# Sheet1.net
KiCad netlist of a schematic drawn in Altium Designer
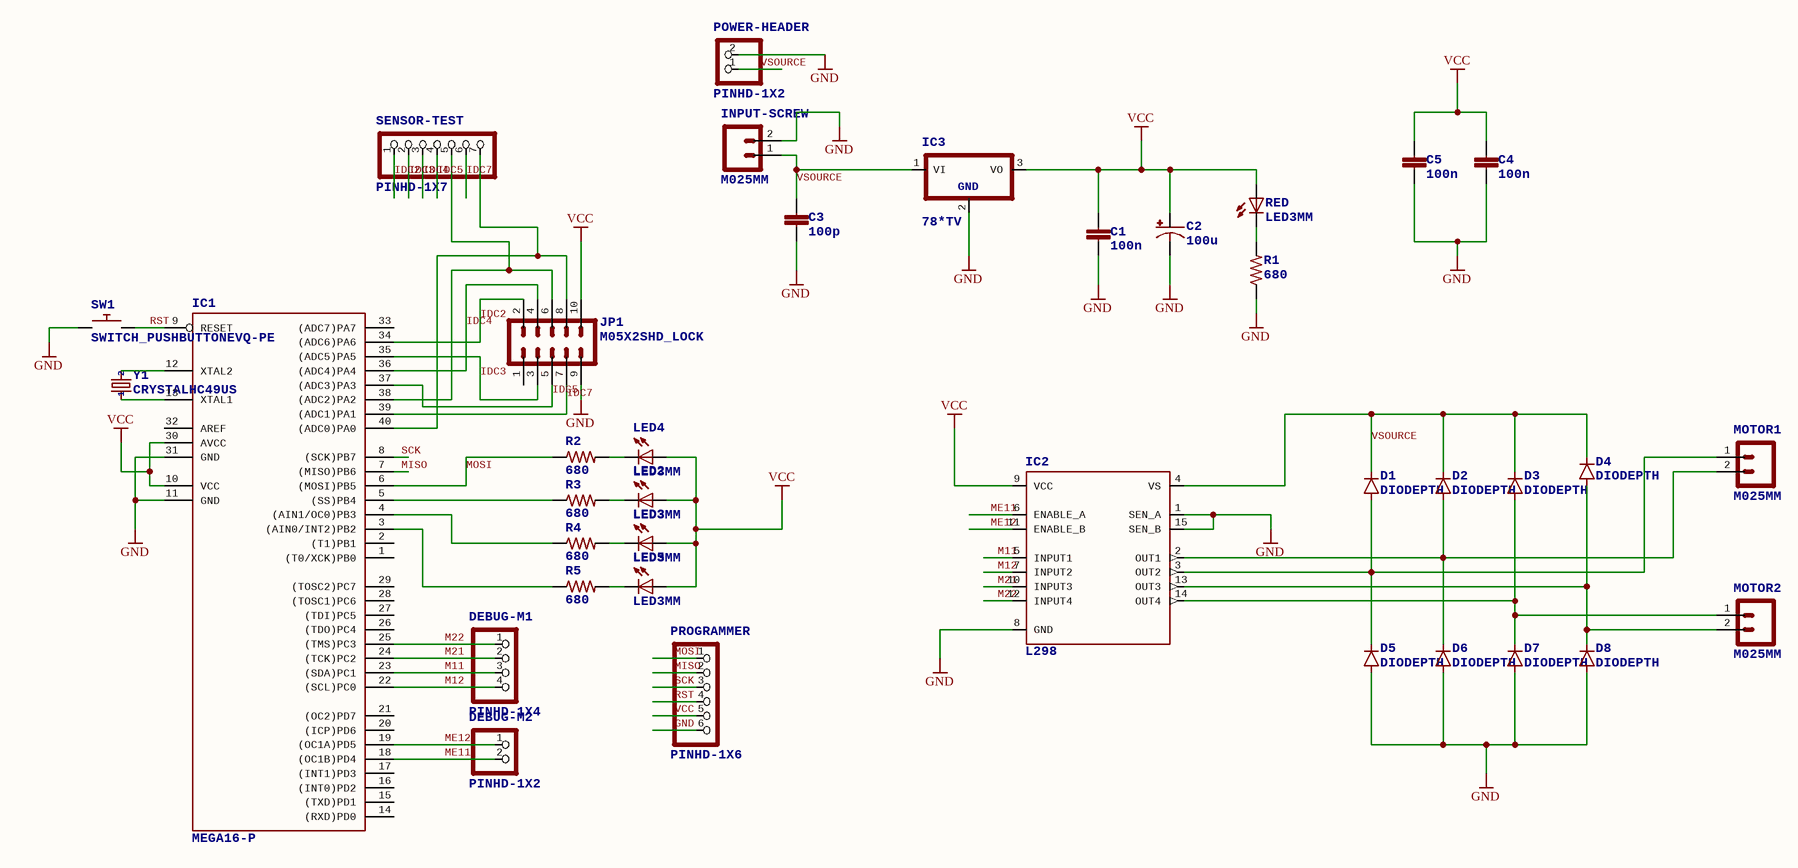
[diagram p0: Sheet1.SchDoc]

(export (version "E")
  (design (tool "Eeschema 10.0.6"))
  (components
    (comp (ref "C1")
      (value "100n")
      (footprint "CAP-PTH-SMALL")
      (description "CapacitorStandard 0603 ceramic capacitor, and 0.1\" leaded capacitor.")
      (libsource (lib "SparkFun-Passives") (part "CAPPTH"))
    )
    (comp (ref "C2")
      (value "100u")
      (footprint "CPOL-RADIAL-100UF-25V")
      (libsource (lib "SparkFun-Passives") (part "CAP_POLPTH1"))
    )
    (comp (ref "C3")
      (value "100p")
      (footprint "CAP-PTH-SMALL")
      (description "CapacitorStandard 0603 ceramic capacitor, and 0.1\" leaded capacitor.")
      (libsource (lib "") (part "CAPPTH_1"))
    )
    (comp (ref "C4")
      (value "100n")
      (footprint "CAP-PTH-SMALL")
      (description "CapacitorStandard 0603 ceramic capacitor, and 0.1\" leaded capacitor.")
      (libsource (lib "SparkFun-Capacitors") (part "CAPPTH"))
    )
    (comp (ref "C5")
      (value "100n")
      (footprint "CAP-PTH-SMALL")
      (description "CapacitorStandard 0603 ceramic capacitor, and 0.1\" leaded capacitor.")
      (libsource (lib "SparkFun-Capacitors") (part "CAPPTH"))
    )
    (comp (ref "D1")
      (value "DIODEPTH")
      (footprint "DIODE-1N4001")
      (libsource (lib "SparkFun-DiscreteSemi") (part "DIODEPTH"))
    )
    (comp (ref "D2")
      (value "DIODEPTH")
      (footprint "DIODE-1N4001")
      (libsource (lib "SparkFun-DiscreteSemi") (part "DIODEPTH"))
    )
    (comp (ref "D3")
      (value "DIODEPTH")
      (footprint "DIODE-1N4001")
      (libsource (lib "SparkFun-DiscreteSemi") (part "DIODEPTH"))
    )
    (comp (ref "D4")
      (value "DIODEPTH")
      (footprint "DIODE-1N4001")
      (libsource (lib "SparkFun-DiscreteSemi") (part "DIODEPTH"))
    )
    (comp (ref "D5")
      (value "DIODEPTH")
      (footprint "DIODE-1N4001")
      (libsource (lib "SparkFun-DiscreteSemi") (part "DIODEPTH"))
    )
    (comp (ref "D6")
      (value "DIODEPTH")
      (footprint "DIODE-1N4001")
      (libsource (lib "SparkFun-DiscreteSemi") (part "DIODEPTH"))
    )
    (comp (ref "D7")
      (value "DIODEPTH")
      (footprint "DIODE-1N4001")
      (libsource (lib "SparkFun-DiscreteSemi") (part "DIODEPTH"))
    )
    (comp (ref "D8")
      (value "DIODEPTH")
      (footprint "DIODE-1N4001")
      (libsource (lib "SparkFun-DiscreteSemi") (part "DIODEPTH"))
    )
    (comp (ref "DEBUG-M1")
      (value "PINHD-1X4")
      (footprint "1X04")
      (description "PIN HEADER")
      (libsource (lib "pinhead") (part "PINHD-1X4"))
    )
    (comp (ref "DEBUG-M2")
      (value "PINHD-1X2")
      (footprint "1X02")
      (description "PIN HEADER")
      (libsource (lib "pinhead") (part "PINHD-1X2"))
    )
    (comp (ref "IC1")
      (value "MEGA16-P")
      (footprint "DIL40")
      (fields (field (name "MPN") "ATMEGA16-16PU"))
      (libsource (lib "atmel") (part "MEGA16-P"))
    )
    (comp (ref "IC2")
      (value "L298")
      (footprint "MULTIWATT-15")
      (description "DUAL FULL-BRIDGE DRIVER")
      (fields (field (name "MPN") "L298N"))
      (libsource (lib "st-microelectronics") (part "L298"))
    )
    (comp (ref "IC3")
      (value "78*TV")
      (footprint "TO220V")
      (fields (field (name "GND") "GND"))
      (libsource (lib "linear") (part "78*TV"))
    )
    (comp (ref "INPUT-SCREW")
      (value "M025MM")
      (footprint "SCREWTERMINAL-5MM-2")
      (libsource (lib "SparkFun-Connectors") (part "M025MM"))
    )
    (comp (ref "JP1")
      (value "M05X2SHD_LOCK")
      (footprint "2X5-SHROUDED_LOCK")
      (libsource (lib "SparkFun-Connectors") (part "M05X2SHD_LOCK"))
    )
    (comp (ref "LED2") (value "LED3MM") (footprint "LED3MM") (libsource (lib "adafruit") (part "LED3MM")))
    (comp (ref "LED3") (value "LED3MM") (footprint "LED3MM") (libsource (lib "adafruit") (part "LED3MM")))
    (comp (ref "LED4") (value "LED3MM") (footprint "LED3MM") (libsource (lib "adafruit") (part "LED3MM")))
    (comp (ref "LED5") (value "LED3MM") (footprint "LED3MM") (libsource (lib "adafruit") (part "LED3MM")))
    (comp (ref "MOTOR1")
      (value "M025MM")
      (footprint "SCREWTERMINAL-5MM-2")
      (libsource (lib "SparkFun-Connectors") (part "M025MM"))
    )
    (comp (ref "MOTOR2")
      (value "M025MM")
      (footprint "SCREWTERMINAL-5MM-2")
      (libsource (lib "SparkFun-Connectors") (part "M025MM"))
    )
    (comp (ref "POWER-HEADER")
      (value "PINHD-1X2")
      (footprint "1X02")
      (description "PIN HEADER")
      (libsource (lib "pinhead") (part "PINHD-1X2"))
    )
    (comp (ref "PROGRAMMER")
      (value "PINHD-1X6")
      (footprint "1X06")
      (description "PIN HEADER")
      (libsource (lib "adafruit") (part "PINHD-1X6"))
    )
    (comp (ref "R1")
      (value "680")
      (footprint "AXIAL-0.3")
      (description "RES-12182")
      (libsource (lib "SparkFun-Resistors") (part "1KOHM-1/4W-1%(PTH)"))
    )
    (comp (ref "R2")
      (value "680")
      (footprint "AXIAL-0.3")
      (description "RES-12182")
      (libsource (lib "SparkFun-Resistors") (part "1KOHM-1/4W-1%(PTH)"))
    )
    (comp (ref "R3")
      (value "680")
      (footprint "AXIAL-0.3")
      (description "RES-12182")
      (libsource (lib "SparkFun-Resistors") (part "1KOHM-1/4W-1%(PTH)"))
    )
    (comp (ref "R4")
      (value "680")
      (footprint "AXIAL-0.3")
      (description "RES-12182")
      (libsource (lib "SparkFun-Resistors") (part "1KOHM-1/4W-1%(PTH)"))
    )
    (comp (ref "R5")
      (value "680")
      (footprint "AXIAL-0.3")
      (description "RES-12182")
      (libsource (lib "SparkFun-Resistors") (part "1KOHM-1/4W-1%(PTH)"))
    )
    (comp (ref "RED") (value "LED3MM") (footprint "LED3MM") (libsource (lib "adafruit") (part "LED3MM")))
    (comp (ref "SENSOR-TEST")
      (value "PINHD-1X7")
      (footprint "1x07")
      (description "PIN HEADER")
      (libsource (lib "pinhead") (part "PINHD-1X7"))
    )
    (comp (ref "SW1")
      (value "SWITCH_PUSHBUTTONEVQ-PE")
      (footprint "TACT_PANA-EVQ")
      (libsource (lib "adafruit") (part "SWITCH_PUSHBUTTONEVQ-PE"))
    )
    (comp (ref "Y1")
      (value "CRYSTALHC49US")
      (footprint "HC49US")
      (description "Various standard crystals. Proven footprints.")
      (fields (field (name "1") "1") (field (name "2") "2"))
      (libsource (lib "SparkFun-FreqCtrl") (part "CRYSTALHC49US"))
    )
  )
  (nets
    (net (code "1") (name "/IDC2") (class "Default")
      (node (ref "IC1") (pin "34") (pinfunction "(ADC6)PA6_34") (pintype "passive"))
      (node (ref "JP1") (pin "2") (pinfunction "2_2") (pintype "passive"))
      (node (ref "SENSOR-TEST") (pin "1") (pinfunction "1_1") (pintype "passive"))
    )
    (net (code "2") (name "/IDC3") (class "Default")
      (node (ref "IC1") (pin "35") (pinfunction "(ADC5)PA5_35") (pintype "passive"))
      (node (ref "JP1") (pin "3") (pinfunction "3_3") (pintype "passive"))
      (node (ref "SENSOR-TEST") (pin "2") (pinfunction "2_2") (pintype "passive"))
    )
    (net (code "3") (name "/IDC4") (class "Default")
      (node (ref "IC1") (pin "36") (pinfunction "(ADC4)PA4_36") (pintype "passive"))
      (node (ref "JP1") (pin "4") (pinfunction "4_4") (pintype "passive"))
      (node (ref "SENSOR-TEST") (pin "3") (pinfunction "3_3") (pintype "passive"))
    )
    (net (code "4") (name "/IDC5") (class "Default")
      (node (ref "IC1") (pin "37") (pinfunction "(ADC3)PA3_37") (pintype "passive"))
      (node (ref "JP1") (pin "5") (pinfunction "5_5") (pintype "passive"))
      (node (ref "SENSOR-TEST") (pin "4") (pinfunction "4_4") (pintype "passive"))
    )
    (net (code "5") (name "/IDC7") (class "Default")
      (node (ref "IC1") (pin "39") (pinfunction "(ADC1)PA1_39") (pintype "passive"))
      (node (ref "JP1") (pin "7") (pinfunction "7_7") (pintype "passive"))
      (node (ref "SENSOR-TEST") (pin "6") (pinfunction "6_6") (pintype "passive"))
    )
    (net (code "6") (name "/M11") (class "Default")
      (node (ref "DEBUG-M1") (pin "3") (pinfunction "3_3") (pintype "passive"))
      (node (ref "IC1") (pin "23") (pinfunction "(SDA)PC1_23") (pintype "passive"))
      (node (ref "IC2") (pin "5") (pinfunction "INPUT1_5") (pintype "passive"))
    )
    (net (code "7") (name "/M12") (class "Default")
      (node (ref "DEBUG-M1") (pin "4") (pinfunction "4_4") (pintype "passive"))
      (node (ref "IC1") (pin "22") (pinfunction "(SCL)PC0_22") (pintype "passive"))
      (node (ref "IC2") (pin "7") (pinfunction "INPUT2_7") (pintype "passive"))
    )
    (net (code "8") (name "/M21") (class "Default")
      (node (ref "DEBUG-M1") (pin "2") (pinfunction "2_2") (pintype "passive"))
      (node (ref "IC1") (pin "24") (pinfunction "(TCK)PC2_24") (pintype "passive"))
      (node (ref "IC2") (pin "10") (pinfunction "INPUT3_10") (pintype "passive"))
    )
    (net (code "9") (name "/M22") (class "Default")
      (node (ref "DEBUG-M1") (pin "1") (pinfunction "1_1") (pintype "passive"))
      (node (ref "IC1") (pin "25") (pinfunction "(TMS)PC3_25") (pintype "passive"))
      (node (ref "IC2") (pin "12") (pinfunction "INPUT4_12") (pintype "passive"))
    )
    (net (code "10") (name "/ME11") (class "Default")
      (node (ref "DEBUG-M2") (pin "2") (pinfunction "2_2") (pintype "passive"))
      (node (ref "IC1") (pin "18") (pinfunction "(OC1B)PD4_18") (pintype "passive"))
      (node (ref "IC2") (pin "6") (pinfunction "ENABLE_A_6") (pintype "passive"))
    )
    (net (code "11") (name "/ME12") (class "Default")
      (node (ref "DEBUG-M2") (pin "1") (pinfunction "1_1") (pintype "passive"))
      (node (ref "IC1") (pin "19") (pinfunction "(OC1A)PD5_19") (pintype "passive"))
      (node (ref "IC2") (pin "11") (pinfunction "ENABLE_B_11") (pintype "passive"))
    )
    (net (code "12") (name "/MISO") (class "Default")
      (node (ref "IC1") (pin "7") (pinfunction "(MISO)PB6_7") (pintype "passive"))
      (node (ref "PROGRAMMER") (pin "2") (pinfunction "2_2") (pintype "passive"))
    )
    (net (code "13") (name "/MOSI") (class "Default")
      (node (ref "IC1") (pin "6") (pinfunction "(MOSI)PB5_6") (pintype "passive"))
      (node (ref "PROGRAMMER") (pin "1") (pinfunction "1_1") (pintype "passive"))
      (node (ref "R2") (pin "P$1") (pinfunction "1_P$1") (pintype "passive"))
    )
    (net (code "14") (name "/RST") (class "Default")
      (node (ref "IC1") (pin "9") (pinfunction "RESET_9") (pintype "passive"))
      (node (ref "PROGRAMMER") (pin "4") (pinfunction "4_4") (pintype "passive"))
      (node (ref "SW1") (pin "P$2") (pinfunction "P$2_P$2") (pintype "passive"))
    )
    (net (code "15") (name "/SCK") (class "Default")
      (node (ref "IC1") (pin "8") (pinfunction "(SCK)PB7_8") (pintype "passive"))
      (node (ref "PROGRAMMER") (pin "3") (pinfunction "3_3") (pintype "passive"))
    )
    (net (code "16") (name "/VSOURCE") (class "Default")
      (node (ref "C3") (pin "2") (pinfunction "2_2") (pintype "passive"))
      (node (ref "D1") (pin "C") (pinfunction "C_C") (pintype "passive"))
      (node (ref "D2") (pin "C") (pinfunction "C_C") (pintype "passive"))
      (node (ref "D3") (pin "C") (pinfunction "C_C") (pintype "passive"))
      (node (ref "D4") (pin "C") (pinfunction "C_C") (pintype "passive"))
      (node (ref "IC2") (pin "4") (pinfunction "VS_4") (pintype "power_in"))
      (node (ref "IC3") (pin "1") (pinfunction "VI_1") (pintype "passive"))
      (node (ref "INPUT-SCREW") (pin "1") (pinfunction "1_1") (pintype "passive"))
      (node (ref "POWER-HEADER") (pin "1") (pinfunction "1_1") (pintype "passive"))
    )
    (net (code "17") (name "GND") (class "Default")
      (node (ref "C1") (pin "2") (pinfunction "2_2") (pintype "passive"))
      (node (ref "C2") (pin "2") (pinfunction "-_2") (pintype "passive"))
      (node (ref "C3") (pin "1") (pinfunction "1_1") (pintype "passive"))
      (node (ref "C4") (pin "2") (pinfunction "2_2") (pintype "passive"))
      (node (ref "C5") (pin "2") (pinfunction "2_2") (pintype "passive"))
      (node (ref "D5") (pin "A") (pinfunction "A_A") (pintype "passive"))
      (node (ref "D6") (pin "A") (pinfunction "A_A") (pintype "passive"))
      (node (ref "D7") (pin "A") (pinfunction "A_A") (pintype "passive"))
      (node (ref "D8") (pin "A") (pinfunction "A_A") (pintype "passive"))
      (node (ref "IC1") (pin "11") (pinfunction "GND_11") (pintype "power_in"))
      (node (ref "IC1") (pin "31") (pinfunction "GND_31") (pintype "power_in"))
      (node (ref "IC2") (pin "1") (pinfunction "SEN_A_1") (pintype "passive"))
      (node (ref "IC2") (pin "15") (pinfunction "SEN_B_15") (pintype "passive"))
      (node (ref "IC2") (pin "8") (pinfunction "GND_8") (pintype "power_in"))
      (node (ref "IC3") (pin "2") (pinfunction "GND_2") (pintype "passive"))
      (node (ref "INPUT-SCREW") (pin "2") (pinfunction "2_2") (pintype "passive"))
      (node (ref "JP1") (pin "9") (pinfunction "9_9") (pintype "passive"))
      (node (ref "POWER-HEADER") (pin "2") (pinfunction "2_2") (pintype "passive"))
      (node (ref "PROGRAMMER") (pin "6") (pinfunction "6_6") (pintype "passive"))
      (node (ref "R1") (pin "P$1") (pinfunction "1_P$1") (pintype "passive"))
      (node (ref "SW1") (pin "P$1") (pinfunction "P$1_P$1") (pintype "passive"))
    )
    (net (code "18") (name "Net-(IC1-(ADC0)PA0)") (class "Default")
      (node (ref "IC1") (pin "40") (pinfunction "(ADC0)PA0_40") (pintype "passive"))
      (node (ref "JP1") (pin "8") (pinfunction "8_8") (pintype "passive"))
      (node (ref "SENSOR-TEST") (pin "7") (pinfunction "7_7") (pintype "passive"))
    )
    (net (code "19") (name "Net-(IC1-(ADC2)PA2)") (class "Default")
      (node (ref "IC1") (pin "38") (pinfunction "(ADC2)PA2_38") (pintype "passive"))
      (node (ref "JP1") (pin "6") (pinfunction "6_6") (pintype "passive"))
      (node (ref "SENSOR-TEST") (pin "5") (pinfunction "5_5") (pintype "passive"))
    )
    (net (code "20") (name "Net-(IC1-(AIN0{slash}INT2)PB2)") (class "Default")
      (node (ref "IC1") (pin "3") (pinfunction "(AIN0/INT2)PB2_3") (pintype "passive"))
      (node (ref "R5") (pin "P$1") (pinfunction "1_P$1") (pintype "passive"))
    )
    (net (code "21") (name "Net-(IC1-(AIN1{slash}OC0)PB3)") (class "Default")
      (node (ref "IC1") (pin "4") (pinfunction "(AIN1/OC0)PB3_4") (pintype "passive"))
      (node (ref "R4") (pin "P$1") (pinfunction "1_P$1") (pintype "passive"))
    )
    (net (code "22") (name "Net-(IC1-(SS)PB4)") (class "Default")
      (node (ref "IC1") (pin "5") (pinfunction "(SS)PB4_5") (pintype "passive"))
      (node (ref "R3") (pin "P$1") (pinfunction "1_P$1") (pintype "passive"))
    )
    (net (code "23") (name "Net-(IC1-XTAL1)") (class "Default")
      (node (ref "IC1") (pin "13") (pinfunction "XTAL1_13") (pintype "passive"))
      (node (ref "Y1") (pin "1") (pinfunction "1_1") (pintype "passive"))
    )
    (net (code "24") (name "Net-(IC1-XTAL2)") (class "Default")
      (node (ref "IC1") (pin "12") (pinfunction "XTAL2_12") (pintype "passive"))
      (node (ref "Y1") (pin "2") (pinfunction "2_2") (pintype "passive"))
    )
    (net (code "25") (name "Net-(IC2-OUT1)") (class "Default")
      (node (ref "D2") (pin "A") (pinfunction "A_A") (pintype "passive"))
      (node (ref "D6") (pin "C") (pinfunction "C_C") (pintype "passive"))
      (node (ref "IC2") (pin "2") (pinfunction "OUT1_2") (pintype "output"))
      (node (ref "MOTOR1") (pin "2") (pinfunction "2_2") (pintype "passive"))
    )
    (net (code "26") (name "Net-(IC2-OUT2)") (class "Default")
      (node (ref "D1") (pin "A") (pinfunction "A_A") (pintype "passive"))
      (node (ref "D5") (pin "C") (pinfunction "C_C") (pintype "passive"))
      (node (ref "IC2") (pin "3") (pinfunction "OUT2_3") (pintype "output"))
      (node (ref "MOTOR1") (pin "1") (pinfunction "1_1") (pintype "passive"))
    )
    (net (code "27") (name "Net-(IC2-OUT3)") (class "Default")
      (node (ref "D4") (pin "A") (pinfunction "A_A") (pintype "passive"))
      (node (ref "D8") (pin "C") (pinfunction "C_C") (pintype "passive"))
      (node (ref "IC2") (pin "13") (pinfunction "OUT3_13") (pintype "output"))
      (node (ref "MOTOR2") (pin "2") (pinfunction "2_2") (pintype "passive"))
    )
    (net (code "28") (name "Net-(IC2-OUT4)") (class "Default")
      (node (ref "D3") (pin "A") (pinfunction "A_A") (pintype "passive"))
      (node (ref "D7") (pin "C") (pinfunction "C_C") (pintype "passive"))
      (node (ref "IC2") (pin "14") (pinfunction "OUT4_14") (pintype "output"))
      (node (ref "MOTOR2") (pin "1") (pinfunction "1_1") (pintype "passive"))
    )
    (net (code "29") (name "Net-(LED2-C)") (class "Default")
      (node (ref "LED2") (pin "K") (pinfunction "C_K") (pintype "passive"))
      (node (ref "R3") (pin "P$2") (pinfunction "2_P$2") (pintype "passive"))
    )
    (net (code "30") (name "Net-(LED3-C)") (class "Default")
      (node (ref "LED3") (pin "K") (pinfunction "C_K") (pintype "passive"))
      (node (ref "R4") (pin "P$2") (pinfunction "2_P$2") (pintype "passive"))
    )
    (net (code "31") (name "Net-(LED4-C)") (class "Default")
      (node (ref "LED4") (pin "K") (pinfunction "C_K") (pintype "passive"))
      (node (ref "R2") (pin "P$2") (pinfunction "2_P$2") (pintype "passive"))
    )
    (net (code "32") (name "Net-(LED5-C)") (class "Default")
      (node (ref "LED5") (pin "K") (pinfunction "C_K") (pintype "passive"))
      (node (ref "R5") (pin "P$2") (pinfunction "2_P$2") (pintype "passive"))
    )
    (net (code "33") (name "Net-(R1-2)") (class "Default")
      (node (ref "R1") (pin "P$2") (pinfunction "2_P$2") (pintype "passive"))
      (node (ref "RED") (pin "K") (pinfunction "C_K") (pintype "passive"))
    )
    (net (code "34") (name "VCC") (class "Default")
      (node (ref "C1") (pin "1") (pinfunction "1_1") (pintype "passive"))
      (node (ref "C2") (pin "1") (pinfunction "+_1") (pintype "passive"))
      (node (ref "C4") (pin "1") (pinfunction "1_1") (pintype "passive"))
      (node (ref "C5") (pin "1") (pinfunction "1_1") (pintype "passive"))
      (node (ref "IC1") (pin "10") (pinfunction "VCC_10") (pintype "power_in"))
      (node (ref "IC1") (pin "30") (pinfunction "AVCC_30") (pintype "power_in"))
      (node (ref "IC2") (pin "9") (pinfunction "VCC_9") (pintype "power_in"))
      (node (ref "IC3") (pin "3") (pinfunction "VO_3") (pintype "passive"))
      (node (ref "JP1") (pin "10") (pinfunction "10_10") (pintype "passive"))
      (node (ref "LED2") (pin "A") (pinfunction "A_A") (pintype "passive"))
      (node (ref "LED3") (pin "A") (pinfunction "A_A") (pintype "passive"))
      (node (ref "LED4") (pin "A") (pinfunction "A_A") (pintype "passive"))
      (node (ref "LED5") (pin "A") (pinfunction "A_A") (pintype "passive"))
      (node (ref "PROGRAMMER") (pin "5") (pinfunction "5_5") (pintype "passive"))
      (node (ref "RED") (pin "A") (pinfunction "A_A") (pintype "passive"))
    )
    (net (code "35") (name "unconnected-(IC1-(ADC7)PA7-Pad33)") (class "Default")
      (node (ref "IC1") (pin "33") (pinfunction "(ADC7)PA7_33") (pintype "passive"))
    )
    (net (code "36") (name "unconnected-(IC1-(ICP)PD6-Pad20)") (class "Default")
      (node (ref "IC1") (pin "20") (pinfunction "(ICP)PD6_20") (pintype "passive"))
    )
    (net (code "37") (name "unconnected-(IC1-(INT0)PD2-Pad16)") (class "Default")
      (node (ref "IC1") (pin "16") (pinfunction "(INT0)PD2_16") (pintype "passive"))
    )
    (net (code "38") (name "unconnected-(IC1-(INT1)PD3-Pad17)") (class "Default")
      (node (ref "IC1") (pin "17") (pinfunction "(INT1)PD3_17") (pintype "passive"))
    )
    (net (code "39") (name "unconnected-(IC1-(OC2)PD7-Pad21)") (class "Default")
      (node (ref "IC1") (pin "21") (pinfunction "(OC2)PD7_21") (pintype "passive"))
    )
    (net (code "40") (name "unconnected-(IC1-(RXD)PD0-Pad14)") (class "Default")
      (node (ref "IC1") (pin "14") (pinfunction "(RXD)PD0_14") (pintype "passive"))
    )
    (net (code "41") (name "unconnected-(IC1-(T0{slash}XCK)PB0-Pad1)") (class "Default")
      (node (ref "IC1") (pin "1") (pinfunction "(T0/XCK)PB0_1") (pintype "passive"))
    )
    (net (code "42") (name "unconnected-(IC1-(T1)PB1-Pad2)") (class "Default")
      (node (ref "IC1") (pin "2") (pinfunction "(T1)PB1_2") (pintype "passive"))
    )
    (net (code "43") (name "unconnected-(IC1-(TDI)PC5-Pad27)") (class "Default")
      (node (ref "IC1") (pin "27") (pinfunction "(TDI)PC5_27") (pintype "passive"))
    )
    (net (code "44") (name "unconnected-(IC1-(TDO)PC4-Pad26)") (class "Default")
      (node (ref "IC1") (pin "26") (pinfunction "(TDO)PC4_26") (pintype "passive"))
    )
    (net (code "45") (name "unconnected-(IC1-(TOSC1)PC6-Pad28)") (class "Default")
      (node (ref "IC1") (pin "28") (pinfunction "(TOSC1)PC6_28") (pintype "passive"))
    )
    (net (code "46") (name "unconnected-(IC1-(TOSC2)PC7-Pad29)") (class "Default")
      (node (ref "IC1") (pin "29") (pinfunction "(TOSC2)PC7_29") (pintype "passive"))
    )
    (net (code "47") (name "unconnected-(IC1-(TXD)PD1-Pad15)") (class "Default")
      (node (ref "IC1") (pin "15") (pinfunction "(TXD)PD1_15") (pintype "passive"))
    )
    (net (code "48") (name "unconnected-(IC1-AREF-Pad32)") (class "Default")
      (node (ref "IC1") (pin "32") (pinfunction "AREF_32") (pintype "passive"))
    )
    (net (code "49") (name "unconnected-(JP1-Pad1)") (class "Default")
      (node (ref "JP1") (pin "1") (pinfunction "1_1") (pintype "passive"))
    )
  )
)
